# C128_AV-Adapter.net
KiCad netlist of a schematic drawn in EAGLE
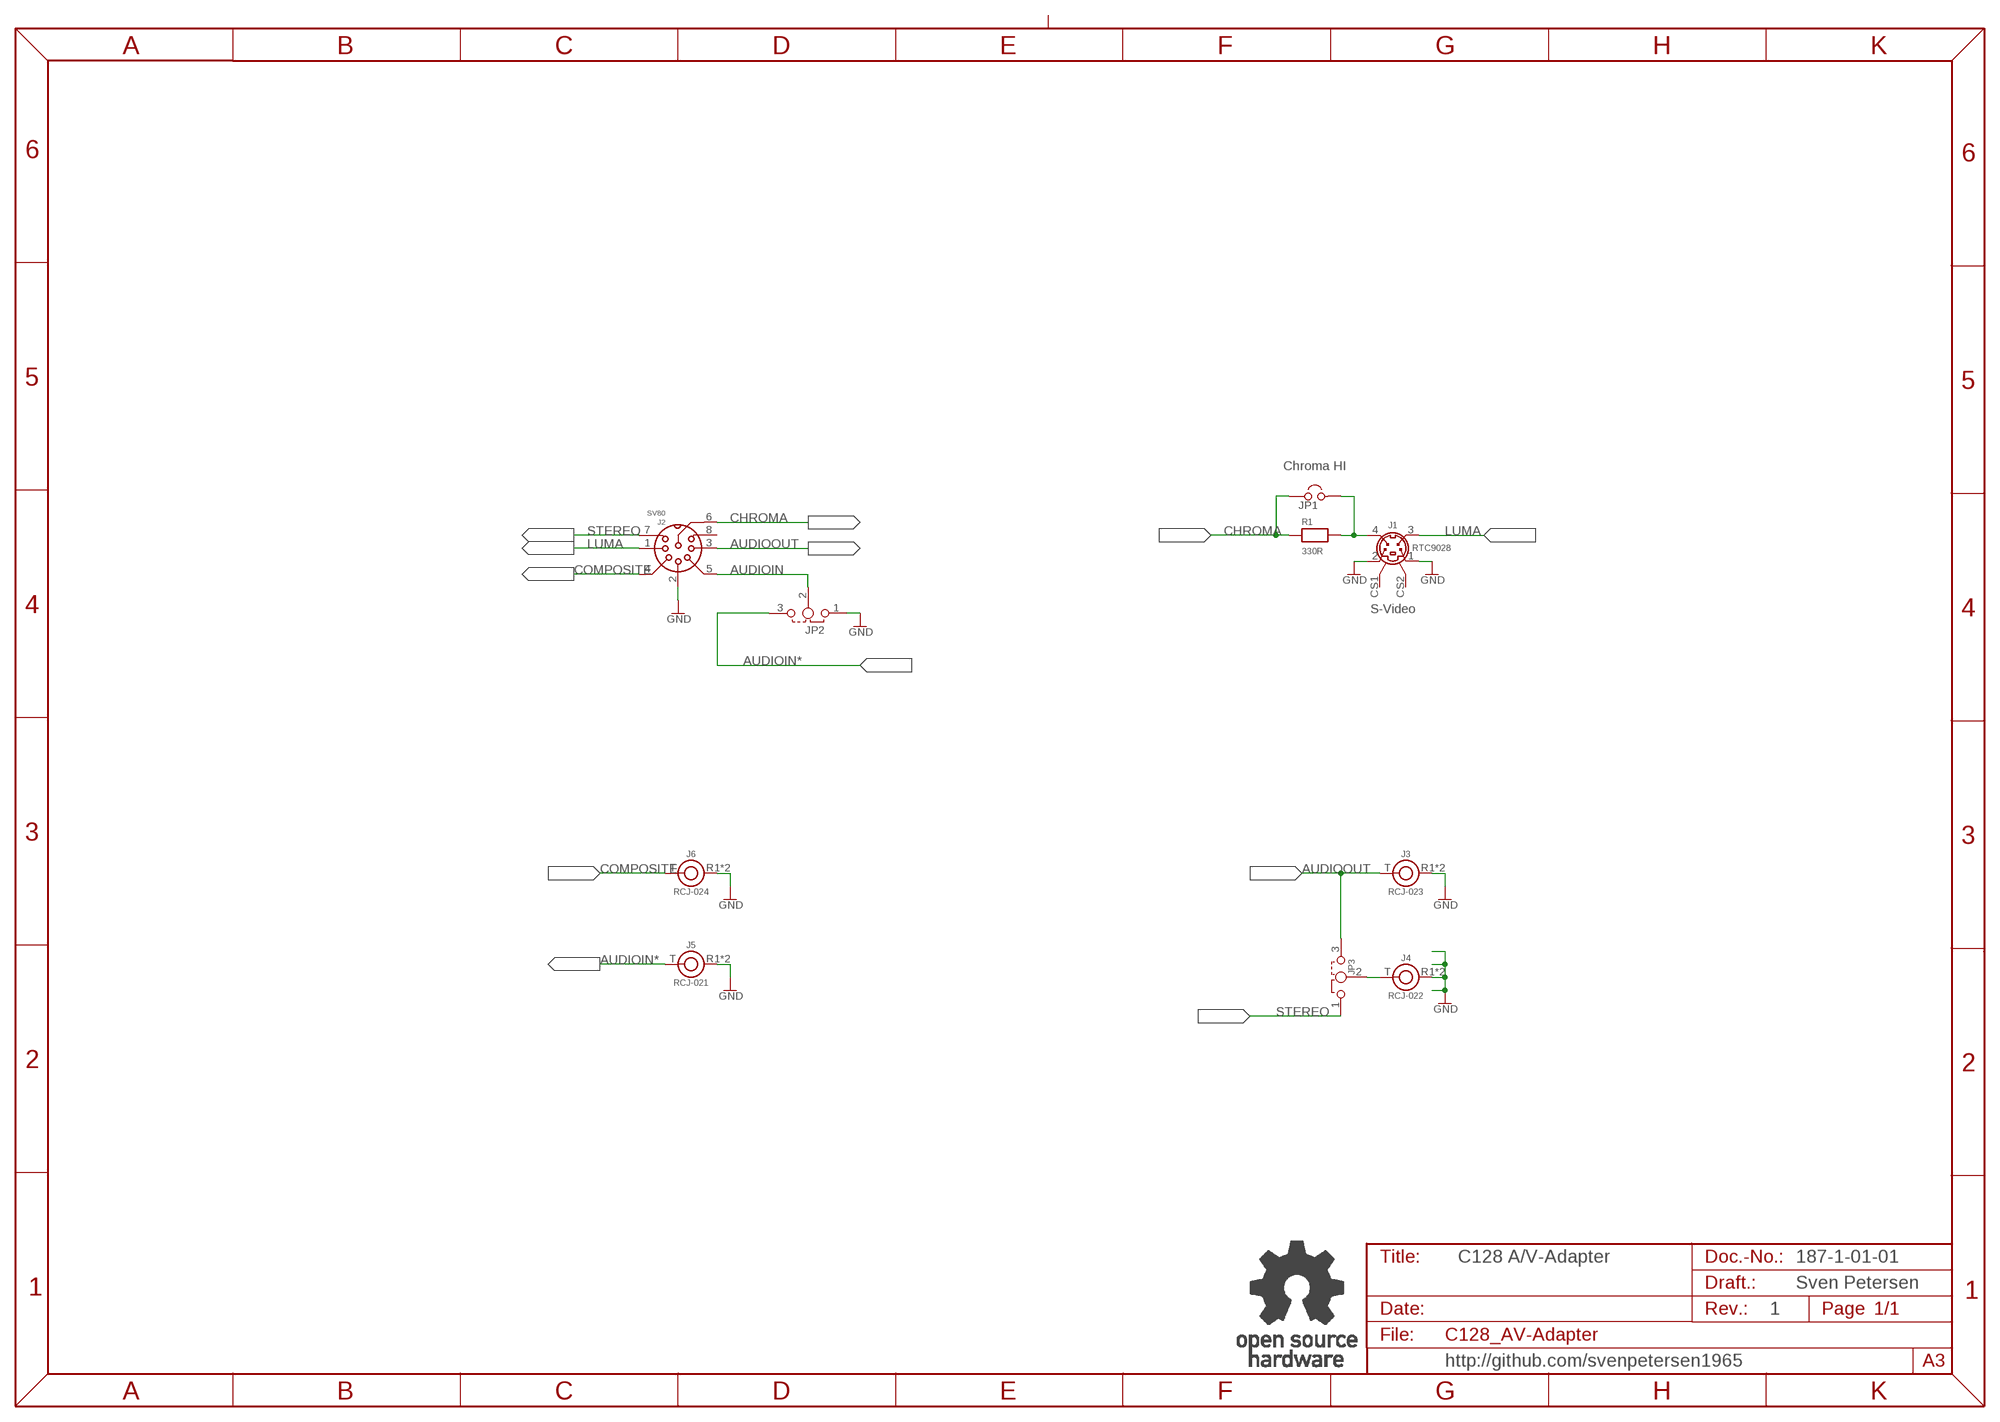
[diagram p0: schematic, sheet 1]

(export (version "E")
  (design (tool "Eeschema 10.0.6"))
  (components
    (comp (ref "J1")
      (value "RTC9028")
      (footprint "eagle-import:MINIDIN4_V")
      (libsource (lib "eagle-import") (part "RTC9028"))
    )
    (comp (ref "J2")
      (value "SV80")
      (footprint "eagle-import:SV80_INNER")
      (libsource (lib "eagle-import") (part "SV80"))
    )
    (comp (ref "J3")
      (value "RCJ-023")
      (footprint "eagle-import:RCJ-02X")
      (libsource (lib "eagle-import") (part "RCJ-02X"))
    )
    (comp (ref "J4")
      (value "RCJ-022")
      (footprint "eagle-import:RCJ-02X")
      (libsource (lib "eagle-import") (part "RCJ-02X"))
    )
    (comp (ref "J5")
      (value "RCJ-021")
      (footprint "eagle-import:RCJ-02X")
      (libsource (lib "eagle-import") (part "RCJ-02X"))
    )
    (comp (ref "J6")
      (value "RCJ-024")
      (footprint "eagle-import:RCJ-02X")
      (libsource (lib "eagle-import") (part "RCJ-02X"))
    )
    (comp (ref "JP1")
      (value "JUMPER")
      (footprint "eagle-import:1X02")
      (libsource (lib "eagle-import") (part "JUMPER"))
    )
    (comp (ref "JP2")
      (value "DJUMPER")
      (footprint "eagle-import:1X03")
      (libsource (lib "eagle-import") (part "DJUMPER"))
    )
    (comp (ref "JP3")
      (value "DJUMPER")
      (footprint "eagle-import:1X03")
      (libsource (lib "eagle-import") (part "DJUMPER"))
    )
    (comp (ref "R1")
      (value "330R")
      (footprint "eagle-import:R-10")
      (libsource (lib "eagle-import") (part "RES04"))
    )
    (comp (ref "U$25")
      (value "OPEN_SOURCE_HW")
      (footprint "eagle-import:OPENHW")
      (libsource (lib "eagle-import") (part "OPEN_SOURCE_HW"))
    )
  )
  (nets
    (net (code "1") (name "/AUDIOIN") (class "Default")
      (node (ref "J2") (pin "5") (pinfunction "5_5") (pintype "bidirectional"))
      (node (ref "JP2") (pin "2") (pinfunction "2_2") (pintype "bidirectional"))
    )
    (net (code "2") (name "/AUDIOIN*") (class "Default")
      (node (ref "J5") (pin "T") (pinfunction "T_T") (pintype "bidirectional"))
      (node (ref "JP2") (pin "3") (pinfunction "3_3") (pintype "bidirectional"))
    )
    (net (code "3") (name "/AUDIOOUT") (class "Default")
      (node (ref "J2") (pin "3") (pinfunction "3_3") (pintype "bidirectional"))
      (node (ref "J3") (pin "T") (pinfunction "T_T") (pintype "bidirectional"))
      (node (ref "JP3") (pin "3") (pinfunction "3_3") (pintype "bidirectional"))
    )
    (net (code "4") (name "/CHROMA") (class "Default")
      (node (ref "J2") (pin "6") (pinfunction "6_6") (pintype "bidirectional"))
      (node (ref "JP1") (pin "1") (pinfunction "1_1") (pintype "bidirectional"))
      (node (ref "R1") (pin "1") (pinfunction "1_1") (pintype "passive"))
    )
    (net (code "5") (name "/COMPOSITE") (class "Default")
      (node (ref "J2") (pin "4") (pinfunction "4_4") (pintype "bidirectional"))
      (node (ref "J6") (pin "T") (pinfunction "T_T") (pintype "bidirectional"))
    )
    (net (code "6") (name "/LUMA") (class "Default")
      (node (ref "J1") (pin "3") (pinfunction "3_3") (pintype "bidirectional"))
      (node (ref "J2") (pin "1") (pinfunction "1_1") (pintype "bidirectional"))
    )
    (net (code "7") (name "/STEREO") (class "Default")
      (node (ref "J2") (pin "7") (pinfunction "7_7") (pintype "bidirectional"))
      (node (ref "JP3") (pin "1") (pinfunction "1_1") (pintype "bidirectional"))
    )
    (net (code "8") (name "GND") (class "Default")
      (node (ref "J1") (pin "1") (pinfunction "1_1") (pintype "bidirectional"))
      (node (ref "J1") (pin "2") (pinfunction "2_2") (pintype "bidirectional"))
      (node (ref "J2") (pin "2") (pinfunction "2_2") (pintype "bidirectional"))
      (node (ref "J3") (pin "R1") (pinfunction "R_R1") (pintype "bidirectional"))
      (node (ref "J3") (pin "R2") (pinfunction "R_R2") (pintype "bidirectional"))
      (node (ref "J4") (pin "R1") (pinfunction "R_R1") (pintype "bidirectional"))
      (node (ref "J4") (pin "R2") (pinfunction "R_R2") (pintype "bidirectional"))
      (node (ref "J5") (pin "R1") (pinfunction "R_R1") (pintype "bidirectional"))
      (node (ref "J5") (pin "R2") (pinfunction "R_R2") (pintype "bidirectional"))
      (node (ref "J6") (pin "R1") (pinfunction "R_R1") (pintype "bidirectional"))
      (node (ref "J6") (pin "R2") (pinfunction "R_R2") (pintype "bidirectional"))
      (node (ref "JP2") (pin "1") (pinfunction "1_1") (pintype "bidirectional"))
    )
    (net (code "9") (name "Net-(J1-Pad4)") (class "Default")
      (node (ref "J1") (pin "4") (pinfunction "4_4") (pintype "bidirectional"))
      (node (ref "JP1") (pin "2") (pinfunction "2_2") (pintype "bidirectional"))
      (node (ref "R1") (pin "2") (pinfunction "2_2") (pintype "passive"))
    )
    (net (code "10") (name "Net-(J4-PadT)") (class "Default")
      (node (ref "J4") (pin "T") (pinfunction "T_T") (pintype "bidirectional"))
      (node (ref "JP3") (pin "2") (pinfunction "2_2") (pintype "bidirectional"))
    )
    (net (code "11") (name "unconnected-(J1-PadCS1)") (class "Default")
      (node (ref "J1") (pin "CS1") (pinfunction "CS1_CS1") (pintype "bidirectional"))
    )
    (net (code "12") (name "unconnected-(J1-PadCS2)") (class "Default")
      (node (ref "J1") (pin "CS2") (pinfunction "CS2_CS2") (pintype "bidirectional"))
    )
    (net (code "13") (name "unconnected-(J2-Pad8)") (class "Default")
      (node (ref "J2") (pin "8") (pinfunction "8_8") (pintype "bidirectional"))
    )
  )
)
